# LED.net
KiCad netlist of a schematic drawn in EAGLE
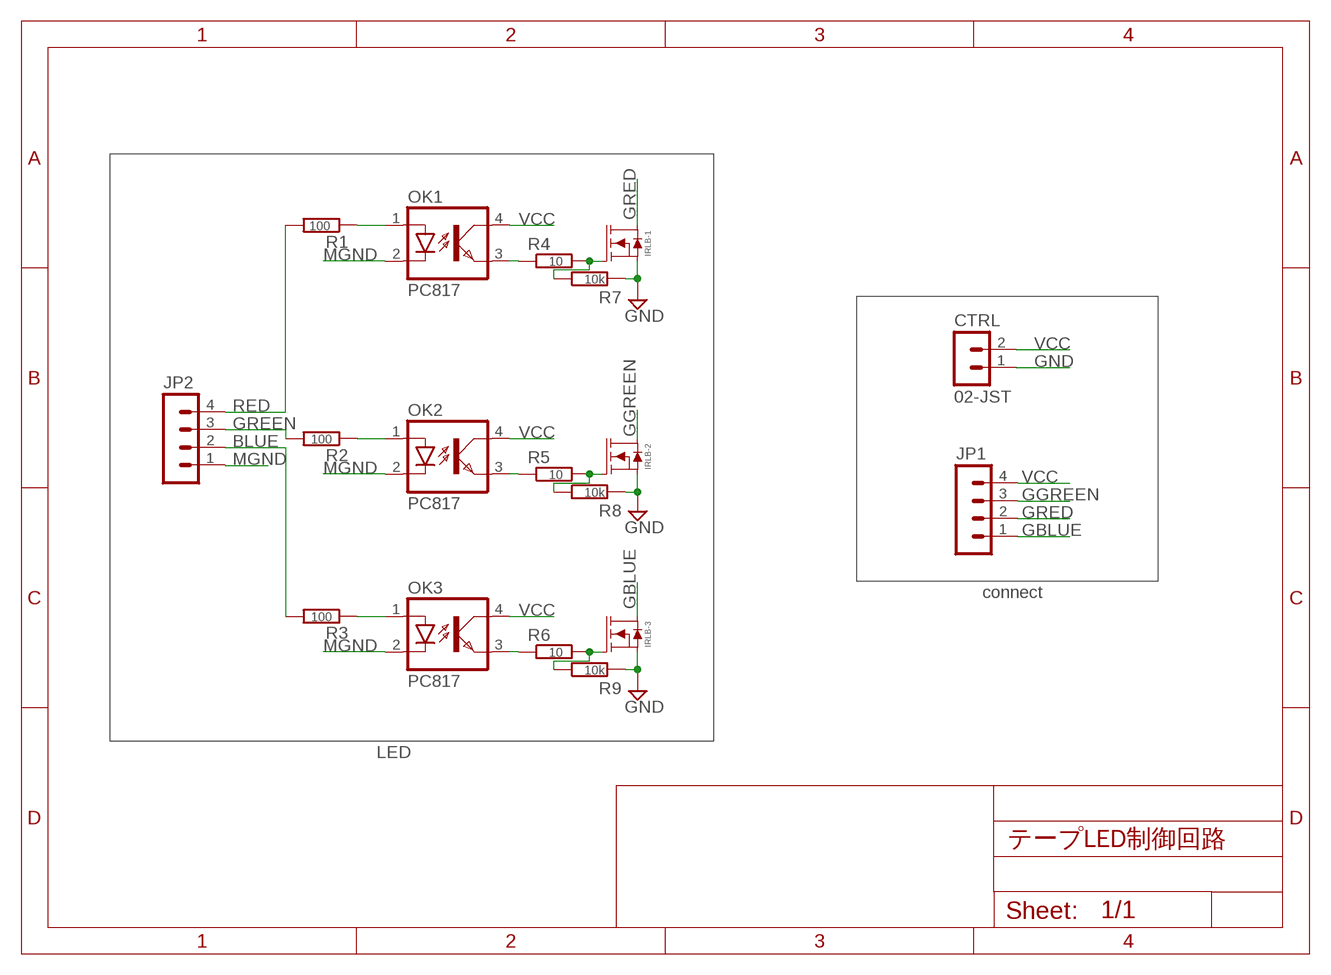
[diagram p0: schematic, sheet 1]

(export (version "E")
  (design (tool "Eeschema 10.0.6"))
  (components
    (comp (ref "CTRL")
      (value "02-JST")
      (footprint "eagle-import:B2B-XH")
      (libsource (lib "eagle-import") (part "02-JST"))
    )
    (comp (ref "IRLB-1")
      (value "IRLB3813STAND")
      (footprint "eagle-import:TO-220AB-STAND")
      (libsource (lib "eagle-import") (part "IRLB3813STAND"))
    )
    (comp (ref "IRLB-2")
      (value "IRLB3813STAND")
      (footprint "eagle-import:TO-220AB-STAND")
      (libsource (lib "eagle-import") (part "IRLB3813STAND"))
    )
    (comp (ref "IRLB-3")
      (value "IRLB3813STAND")
      (footprint "eagle-import:TO-220AB-STAND")
      (libsource (lib "eagle-import") (part "IRLB3813STAND"))
    )
    (comp (ref "JP1")
      (value "04-JST")
      (footprint "eagle-import:B4B-XH")
      (libsource (lib "eagle-import") (part "04-JST"))
    )
    (comp (ref "JP2")
      (value "04-JST")
      (footprint "eagle-import:B4B-XH")
      (libsource (lib "eagle-import") (part "04-JST"))
    )
    (comp (ref "OK1")
      (value "PC817")
      (footprint "eagle-import:DIL04")
      (fields (field (name "MPN") "PC817X4J000F"))
      (libsource (lib "eagle-import") (part "PC817"))
    )
    (comp (ref "OK2")
      (value "PC817")
      (footprint "eagle-import:DIL04")
      (fields (field (name "MPN") "PC817X4J000F"))
      (libsource (lib "eagle-import") (part "PC817"))
    )
    (comp (ref "OK3")
      (value "PC817")
      (footprint "eagle-import:DIL04")
      (fields (field (name "MPN") "PC817X4J000F"))
      (libsource (lib "eagle-import") (part "PC817"))
    )
    (comp (ref "R1")
      (value "100")
      (footprint "eagle-import:0204_7")
      (libsource (lib "eagle-import") (part "R-EU_0204/7"))
    )
    (comp (ref "R2")
      (value "100")
      (footprint "eagle-import:0204_7")
      (libsource (lib "eagle-import") (part "R-EU_0204/7"))
    )
    (comp (ref "R3")
      (value "100")
      (footprint "eagle-import:0204_7")
      (libsource (lib "eagle-import") (part "R-EU_0204/7"))
    )
    (comp (ref "R4")
      (value "10")
      (footprint "eagle-import:0204_7")
      (libsource (lib "eagle-import") (part "R-EU_0204/7"))
    )
    (comp (ref "R5")
      (value "10")
      (footprint "eagle-import:0204_7")
      (libsource (lib "eagle-import") (part "R-EU_0204/7"))
    )
    (comp (ref "R6")
      (value "10")
      (footprint "eagle-import:0204_7")
      (libsource (lib "eagle-import") (part "R-EU_0204/7"))
    )
    (comp (ref "R7")
      (value "10k")
      (footprint "eagle-import:0204_7")
      (libsource (lib "eagle-import") (part "R-EU_0204/7"))
    )
    (comp (ref "R8")
      (value "10k")
      (footprint "eagle-import:0204_7")
      (libsource (lib "eagle-import") (part "R-EU_0204/7"))
    )
    (comp (ref "R9")
      (value "10k")
      (footprint "eagle-import:0204_7")
      (libsource (lib "eagle-import") (part "R-EU_0204/7"))
    )
  )
  (nets
    (net (code "1") (name "/BLUE") (class "Default")
      (node (ref "JP2") (pin "2") (pinfunction "2_2") (pintype "passive"))
      (node (ref "R3") (pin "2") (pinfunction "2_2") (pintype "passive"))
    )
    (net (code "2") (name "/GBLUE") (class "Default")
      (node (ref "IRLB-3") (pin "D") (pinfunction "D_D") (pintype "passive"))
      (node (ref "JP1") (pin "1") (pinfunction "1_1") (pintype "passive"))
    )
    (net (code "3") (name "/GGREEN") (class "Default")
      (node (ref "IRLB-2") (pin "D") (pinfunction "D_D") (pintype "passive"))
      (node (ref "JP1") (pin "3") (pinfunction "3_3") (pintype "passive"))
    )
    (net (code "4") (name "/GRED") (class "Default")
      (node (ref "IRLB-1") (pin "D") (pinfunction "D_D") (pintype "passive"))
      (node (ref "JP1") (pin "2") (pinfunction "2_2") (pintype "passive"))
    )
    (net (code "5") (name "/GREEN") (class "Default")
      (node (ref "JP2") (pin "3") (pinfunction "3_3") (pintype "passive"))
      (node (ref "R2") (pin "2") (pinfunction "2_2") (pintype "passive"))
    )
    (net (code "6") (name "/MGND") (class "Default")
      (node (ref "JP2") (pin "1") (pinfunction "1_1") (pintype "passive"))
      (node (ref "OK1") (pin "2") (pinfunction "C_2") (pintype "passive"))
      (node (ref "OK2") (pin "2") (pinfunction "C_2") (pintype "passive"))
      (node (ref "OK3") (pin "2") (pinfunction "C_2") (pintype "passive"))
    )
    (net (code "7") (name "/RED") (class "Default")
      (node (ref "JP2") (pin "4") (pinfunction "4_4") (pintype "passive"))
      (node (ref "R1") (pin "2") (pinfunction "2_2") (pintype "passive"))
    )
    (net (code "8") (name "/VCC") (class "Default")
      (node (ref "CTRL") (pin "2") (pinfunction "2_2") (pintype "passive"))
      (node (ref "JP1") (pin "4") (pinfunction "4_4") (pintype "passive"))
      (node (ref "OK1") (pin "4") (pinfunction "COL_4") (pintype "passive"))
      (node (ref "OK2") (pin "4") (pinfunction "COL_4") (pintype "passive"))
      (node (ref "OK3") (pin "4") (pinfunction "COL_4") (pintype "passive"))
    )
    (net (code "9") (name "GND") (class "Default")
      (node (ref "CTRL") (pin "1") (pinfunction "1_1") (pintype "passive"))
      (node (ref "IRLB-1") (pin "S") (pinfunction "S_S") (pintype "passive"))
      (node (ref "IRLB-2") (pin "S") (pinfunction "S_S") (pintype "passive"))
      (node (ref "IRLB-3") (pin "S") (pinfunction "S_S") (pintype "passive"))
      (node (ref "R7") (pin "2") (pinfunction "2_2") (pintype "passive"))
      (node (ref "R8") (pin "2") (pinfunction "2_2") (pintype "passive"))
      (node (ref "R9") (pin "2") (pinfunction "2_2") (pintype "passive"))
    )
    (net (code "10") (name "Net-(IRLB-1-PadG)") (class "Default")
      (node (ref "IRLB-1") (pin "G") (pinfunction "G_G") (pintype "passive"))
      (node (ref "R4") (pin "2") (pinfunction "2_2") (pintype "passive"))
      (node (ref "R7") (pin "1") (pinfunction "1_1") (pintype "passive"))
    )
    (net (code "11") (name "Net-(IRLB-2-PadG)") (class "Default")
      (node (ref "IRLB-2") (pin "G") (pinfunction "G_G") (pintype "passive"))
      (node (ref "R5") (pin "2") (pinfunction "2_2") (pintype "passive"))
      (node (ref "R8") (pin "1") (pinfunction "1_1") (pintype "passive"))
    )
    (net (code "12") (name "Net-(IRLB-3-PadG)") (class "Default")
      (node (ref "IRLB-3") (pin "G") (pinfunction "G_G") (pintype "passive"))
      (node (ref "R6") (pin "2") (pinfunction "2_2") (pintype "passive"))
      (node (ref "R9") (pin "1") (pinfunction "1_1") (pintype "passive"))
    )
    (net (code "13") (name "Net-(OK1-A)") (class "Default")
      (node (ref "OK1") (pin "1") (pinfunction "A_1") (pintype "passive"))
      (node (ref "R1") (pin "1") (pinfunction "1_1") (pintype "passive"))
    )
    (net (code "14") (name "Net-(OK1-EMIT)") (class "Default")
      (node (ref "OK1") (pin "3") (pinfunction "EMIT_3") (pintype "passive"))
      (node (ref "R4") (pin "1") (pinfunction "1_1") (pintype "passive"))
    )
    (net (code "15") (name "Net-(OK2-A)") (class "Default")
      (node (ref "OK2") (pin "1") (pinfunction "A_1") (pintype "passive"))
      (node (ref "R2") (pin "1") (pinfunction "1_1") (pintype "passive"))
    )
    (net (code "16") (name "Net-(OK2-EMIT)") (class "Default")
      (node (ref "OK2") (pin "3") (pinfunction "EMIT_3") (pintype "passive"))
      (node (ref "R5") (pin "1") (pinfunction "1_1") (pintype "passive"))
    )
    (net (code "17") (name "Net-(OK3-A)") (class "Default")
      (node (ref "OK3") (pin "1") (pinfunction "A_1") (pintype "passive"))
      (node (ref "R3") (pin "1") (pinfunction "1_1") (pintype "passive"))
    )
    (net (code "18") (name "Net-(OK3-EMIT)") (class "Default")
      (node (ref "OK3") (pin "3") (pinfunction "EMIT_3") (pintype "passive"))
      (node (ref "R6") (pin "1") (pinfunction "1_1") (pintype "passive"))
    )
  )
)
